# atmega328_isp.net
KiCad netlist of a schematic drawn in EAGLE
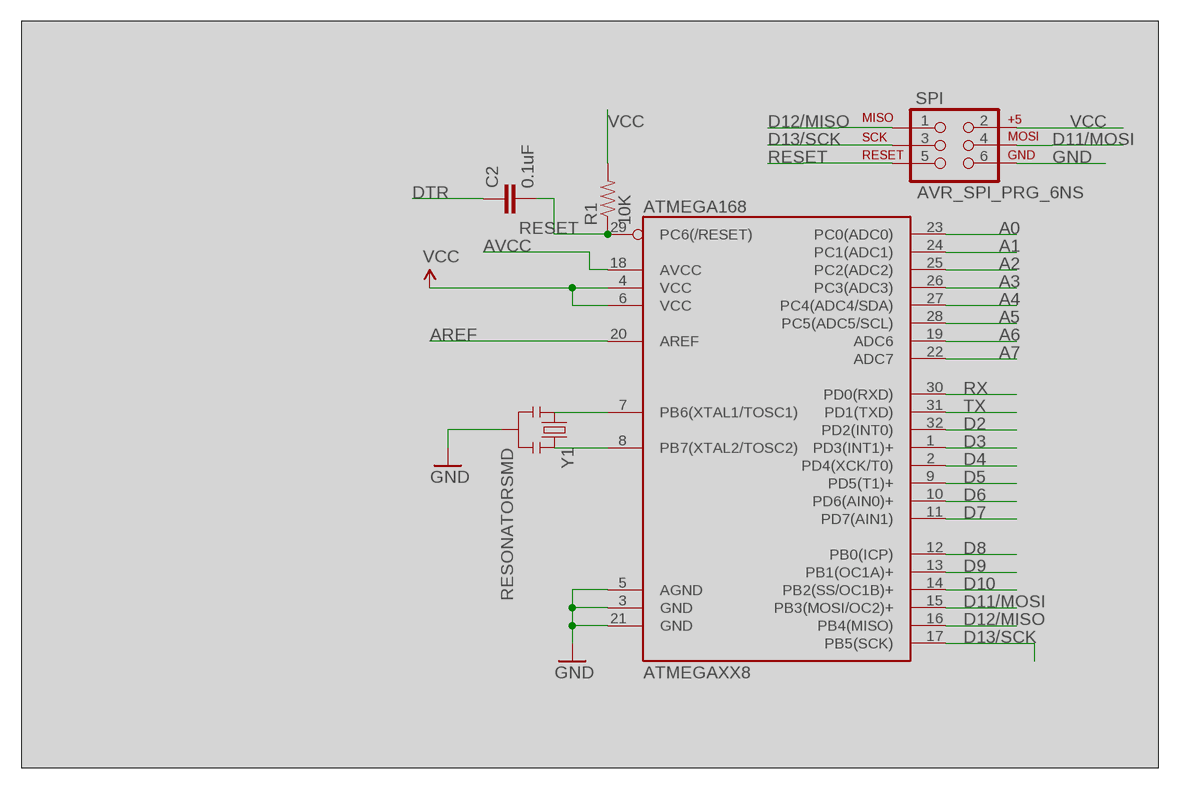
[diagram p0: schematic, sheet 1]

(export (version "E")
  (design (tool "Eeschema 10.0.6"))
  (components
    (comp (ref "ATMEGAXX8")
      (value "ATMEGA168")
      (footprint "eagle-import:TQFP32-08")
      (libsource (lib "eagle-import") (part "ATMEGA168"))
    )
    (comp (ref "C2")
      (value "0.1uF")
      (footprint "eagle-import:0805")
      (libsource (lib "eagle-import") (part "CAP0805"))
    )
    (comp (ref "R1")
      (value "10K")
      (footprint "eagle-import:0805")
      (libsource (lib "eagle-import") (part "RESISTOR0805-RES"))
    )
    (comp (ref "SPI")
      (value "AVR_SPI_PRG_6NS")
      (footprint "eagle-import:2X3-NS")
      (libsource (lib "eagle-import") (part "AVR_SPI_PRG_6NS"))
    )
    (comp (ref "Y1")
      (value "RESONATORSMD")
      (footprint "eagle-import:RESONATOR-SMD")
      (libsource (lib "eagle-import") (part "RESONATORSMD"))
    )
  )
  (nets
    (net (code "1") (name "/A0") (class "Default")
      (node (ref "ATMEGAXX8") (pin "23") (pinfunction "PC0(ADC0)_23") (pintype "bidirectional"))
    )
    (net (code "2") (name "/A1") (class "Default")
      (node (ref "ATMEGAXX8") (pin "24") (pinfunction "PC1(ADC1)_24") (pintype "bidirectional"))
    )
    (net (code "3") (name "/A2") (class "Default")
      (node (ref "ATMEGAXX8") (pin "25") (pinfunction "PC2(ADC2)_25") (pintype "bidirectional"))
    )
    (net (code "4") (name "/A3") (class "Default")
      (node (ref "ATMEGAXX8") (pin "26") (pinfunction "PC3(ADC3)_26") (pintype "bidirectional"))
    )
    (net (code "5") (name "/A4") (class "Default")
      (node (ref "ATMEGAXX8") (pin "27") (pinfunction "PC4(ADC4/SDA)_27") (pintype "bidirectional"))
    )
    (net (code "6") (name "/A5") (class "Default")
      (node (ref "ATMEGAXX8") (pin "28") (pinfunction "PC5(ADC5/SCL)_28") (pintype "bidirectional"))
    )
    (net (code "7") (name "/A6") (class "Default")
      (node (ref "ATMEGAXX8") (pin "19") (pinfunction "ADC6_19") (pintype "bidirectional"))
    )
    (net (code "8") (name "/A7") (class "Default")
      (node (ref "ATMEGAXX8") (pin "22") (pinfunction "ADC7_22") (pintype "bidirectional"))
    )
    (net (code "9") (name "/AREF") (class "Default")
      (node (ref "ATMEGAXX8") (pin "20") (pinfunction "AREF_20") (pintype "bidirectional"))
    )
    (net (code "10") (name "/AVCC") (class "Default")
      (node (ref "ATMEGAXX8") (pin "18") (pinfunction "AVCC_18") (pintype "bidirectional"))
    )
    (net (code "11") (name "/D2") (class "Default")
      (node (ref "ATMEGAXX8") (pin "32") (pinfunction "PD2(INT0)_32") (pintype "bidirectional"))
    )
    (net (code "12") (name "/D3") (class "Default")
      (node (ref "ATMEGAXX8") (pin "1") (pinfunction "PD3(INT1)+_1") (pintype "bidirectional"))
    )
    (net (code "13") (name "/D4") (class "Default")
      (node (ref "ATMEGAXX8") (pin "2") (pinfunction "PD4(XCK/T0)_2") (pintype "bidirectional"))
    )
    (net (code "14") (name "/D5") (class "Default")
      (node (ref "ATMEGAXX8") (pin "9") (pinfunction "PD5(T1)+_9") (pintype "bidirectional"))
    )
    (net (code "15") (name "/D6") (class "Default")
      (node (ref "ATMEGAXX8") (pin "10") (pinfunction "PD6(AIN0)+_10") (pintype "bidirectional"))
    )
    (net (code "16") (name "/D7") (class "Default")
      (node (ref "ATMEGAXX8") (pin "11") (pinfunction "PD7(AIN1)_11") (pintype "bidirectional"))
    )
    (net (code "17") (name "/D8") (class "Default")
      (node (ref "ATMEGAXX8") (pin "12") (pinfunction "PB0(ICP)_12") (pintype "bidirectional"))
    )
    (net (code "18") (name "/D9") (class "Default")
      (node (ref "ATMEGAXX8") (pin "13") (pinfunction "PB1(OC1A)+_13") (pintype "bidirectional"))
    )
    (net (code "19") (name "/D10") (class "Default")
      (node (ref "ATMEGAXX8") (pin "14") (pinfunction "PB2(SS/OC1B)+_14") (pintype "bidirectional"))
    )
    (net (code "20") (name "/D11{slash}MOSI") (class "Default")
      (node (ref "ATMEGAXX8") (pin "15") (pinfunction "PB3(MOSI/OC2)+_15") (pintype "bidirectional"))
      (node (ref "SPI") (pin "4") (pinfunction "4_4") (pintype "passive"))
    )
    (net (code "21") (name "/D12{slash}MISO") (class "Default")
      (node (ref "ATMEGAXX8") (pin "16") (pinfunction "PB4(MISO)_16") (pintype "bidirectional"))
      (node (ref "SPI") (pin "1") (pinfunction "1_1") (pintype "passive"))
    )
    (net (code "22") (name "/D13{slash}SCK") (class "Default")
      (node (ref "ATMEGAXX8") (pin "17") (pinfunction "PB5(SCK)_17") (pintype "bidirectional"))
      (node (ref "SPI") (pin "3") (pinfunction "3_3") (pintype "passive"))
    )
    (net (code "23") (name "/DTR") (class "Default")
      (node (ref "C2") (pin "1") (pinfunction "1_1") (pintype "passive"))
    )
    (net (code "24") (name "/RESET") (class "Default")
      (node (ref "ATMEGAXX8") (pin "29") (pinfunction "PC6(/RESET)_29") (pintype "bidirectional"))
      (node (ref "C2") (pin "2") (pinfunction "2_2") (pintype "passive"))
      (node (ref "R1") (pin "1") (pinfunction "1_1") (pintype "passive"))
      (node (ref "SPI") (pin "5") (pinfunction "5_5") (pintype "passive"))
    )
    (net (code "25") (name "/RX") (class "Default")
      (node (ref "ATMEGAXX8") (pin "30") (pinfunction "PD0(RXD)_30") (pintype "bidirectional"))
    )
    (net (code "26") (name "/TX") (class "Default")
      (node (ref "ATMEGAXX8") (pin "31") (pinfunction "PD1(TXD)_31") (pintype "bidirectional"))
    )
    (net (code "27") (name "GND") (class "Default")
      (node (ref "ATMEGAXX8") (pin "21") (pinfunction "GND_21") (pintype "bidirectional"))
      (node (ref "ATMEGAXX8") (pin "3") (pinfunction "GND_3") (pintype "bidirectional"))
      (node (ref "ATMEGAXX8") (pin "5") (pinfunction "AGND_5") (pintype "bidirectional"))
      (node (ref "SPI") (pin "6") (pinfunction "6_6") (pintype "passive"))
      (node (ref "Y1") (pin "2") (pinfunction "2_2") (pintype "passive"))
    )
    (net (code "28") (name "Net-(ATMEGAXX8-PB6(XTAL1{slash}TOSC1))") (class "Default")
      (node (ref "ATMEGAXX8") (pin "7") (pinfunction "PB6(XTAL1/TOSC1)_7") (pintype "bidirectional"))
      (node (ref "Y1") (pin "1") (pinfunction "1_1") (pintype "passive"))
    )
    (net (code "29") (name "Net-(ATMEGAXX8-PB7(XTAL2{slash}TOSC2))") (class "Default")
      (node (ref "ATMEGAXX8") (pin "8") (pinfunction "PB7(XTAL2/TOSC2)_8") (pintype "bidirectional"))
      (node (ref "Y1") (pin "3") (pinfunction "3_3") (pintype "passive"))
    )
    (net (code "30") (name "VCC") (class "Default")
      (node (ref "ATMEGAXX8") (pin "4") (pinfunction "VCC_4") (pintype "bidirectional"))
      (node (ref "ATMEGAXX8") (pin "6") (pinfunction "VCC_6") (pintype "bidirectional"))
      (node (ref "R1") (pin "2") (pinfunction "2_2") (pintype "passive"))
      (node (ref "SPI") (pin "2") (pinfunction "2_2") (pintype "passive"))
    )
  )
)
